# VESC6_0.net
KiCad netlist of a schematic drawn in Altium Designer
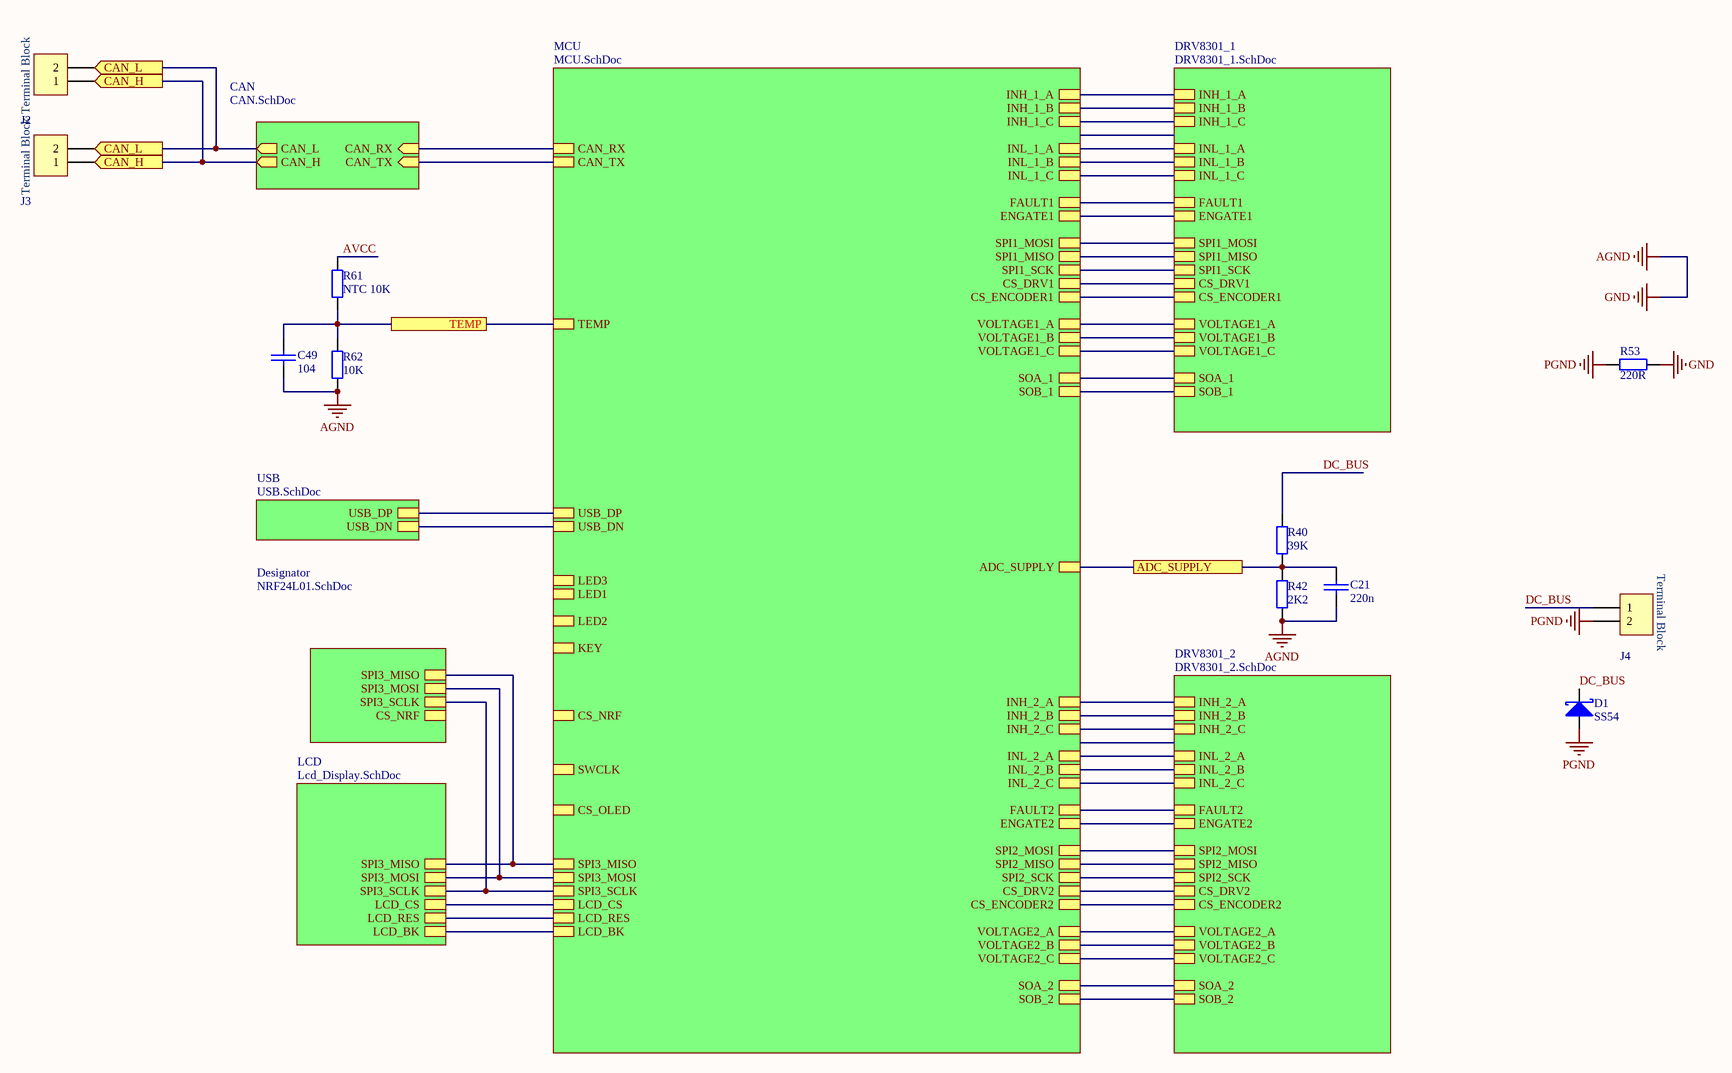
[diagram p0: VESC6.0.SchDoc]

(export (version "E")
  (design (tool "Eeschema 10.0.6"))
  (components
    (comp (ref "C21")
      (value "220n")
      (footprint "0402C")
      (fields (field (name "Comment") "CAP"))
      (libsource (lib "MY SCH LIB__JCH") (part "CAP"))
    )
    (comp (ref "C49")
      (value "104")
      (footprint "0402C")
      (fields (field (name "Comment") "CAP"))
      (libsource (lib "MY SCH LIB__JCH") (part "CAP"))
    )
    (comp (ref "D1")
      (value "SS54")
      (footprint "DIODE_3*5.3")
      (description "Schottky Diode")
      (fields (field (name "PUBLISHER") "Altium Limited"))
      (libsource (lib "FOC") (part "D Schottky"))
    )
    (comp (ref "J2")
      (value "Terminal Block 2P")
      (footprint "A1002WR-S-2P")
      (libsource (lib "") (part "Terminal Block 2P_1"))
    )
    (comp (ref "J3")
      (value "Terminal Block 2P")
      (footprint "A1002WR-S-2P")
      (libsource (lib "") (part "Terminal Block 2P_1"))
    )
    (comp (ref "J4")
      (value "Terminal Block 2P")
      (footprint "POWER")
      (libsource (lib "MY SCH LIB__JCH") (part "Terminal Block 2P"))
    )
    (comp (ref "R40")
      (value "39K")
      (footprint "0402R")
      (description "Resistor")
      (fields (field (name "PUBLISHER") "Altium Limited"))
      (libsource (lib "Miscellaneous Devices") (part "Res2"))
    )
    (comp (ref "R42")
      (value "2K2")
      (footprint "0402R")
      (description "Resistor")
      (fields (field (name "PUBLISHER") "Altium Limited"))
      (libsource (lib "") (part "Res2_2"))
    )
    (comp (ref "R53")
      (value "220R")
      (footprint "1206_R")
      (description "Resistor")
      (fields (field (name "PUBLISHER") "Altium Limited"))
      (libsource (lib "") (part "Res2_1"))
    )
    (comp (ref "R61")
      (value "NTC 10K")
      (footprint "0402R")
      (description "Resistor")
      (fields (field (name "PUBLISHER") "Altium Limited"))
      (libsource (lib "Miscellaneous Devices") (part "Res2"))
    )
    (comp (ref "R62")
      (value "10K")
      (footprint "0402R")
      (description "Resistor")
      (fields (field (name "PUBLISHER") "Altium Limited"))
      (libsource (lib "") (part "Res2_2"))
    )
  )
  (nets
    (net (code "1") (name "/ADC_SUPPLY") (class "Default")
      (node (ref "C21") (pin "1") (pinfunction "1_1") (pintype "passive"))
      (node (ref "R40") (pin "1") (pinfunction "1_1") (pintype "passive"))
      (node (ref "R42") (pin "1") (pinfunction "1_1") (pintype "passive"))
    )
    (net (code "2") (name "/AVCC") (class "Default")
      (node (ref "R61") (pin "2") (pinfunction "2_2") (pintype "passive"))
    )
    (net (code "3") (name "/CAN_H") (class "Default")
      (node (ref "J2") (pin "1") (pinfunction "1_1") (pintype "passive"))
      (node (ref "J3") (pin "1") (pinfunction "1_1") (pintype "passive"))
    )
    (net (code "4") (name "/CAN_L") (class "Default")
      (node (ref "J2") (pin "2") (pinfunction "2_2") (pintype "passive"))
      (node (ref "J3") (pin "2") (pinfunction "2_2") (pintype "passive"))
    )
    (net (code "14") (name "/DC_BUS") (class "Default")
      (node (ref "D1") (pin "2") (pinfunction "K_2") (pintype "passive"))
      (node (ref "J4") (pin "1") (pinfunction "1_1") (pintype "passive"))
      (node (ref "R40") (pin "2") (pinfunction "2_2") (pintype "passive"))
    )
    (net (code "52") (name "/TEMP") (class "Default")
      (node (ref "C49") (pin "1") (pinfunction "1_1") (pintype "passive"))
      (node (ref "R61") (pin "1") (pinfunction "1_1") (pintype "passive"))
      (node (ref "R62") (pin "1") (pinfunction "1_1") (pintype "passive"))
    )
    (net (code "61") (name "AGND") (class "Default")
      (node (ref "C21") (pin "2") (pinfunction "2_2") (pintype "passive"))
      (node (ref "C49") (pin "2") (pinfunction "2_2") (pintype "passive"))
      (node (ref "R42") (pin "2") (pinfunction "2_2") (pintype "passive"))
      (node (ref "R53") (pin "2") (pinfunction "2_2") (pintype "passive"))
      (node (ref "R62") (pin "2") (pinfunction "2_2") (pintype "passive"))
    )
    (net (code "62") (name "PGND") (class "Default")
      (node (ref "D1") (pin "1") (pinfunction "A_1") (pintype "passive"))
      (node (ref "J4") (pin "2") (pinfunction "2_2") (pintype "passive"))
      (node (ref "R53") (pin "1") (pinfunction "1_1") (pintype "passive"))
    )
  )
)
